# sch_design_easyEDA.net
KiCad netlist of a schematic drawn in EasyEDA
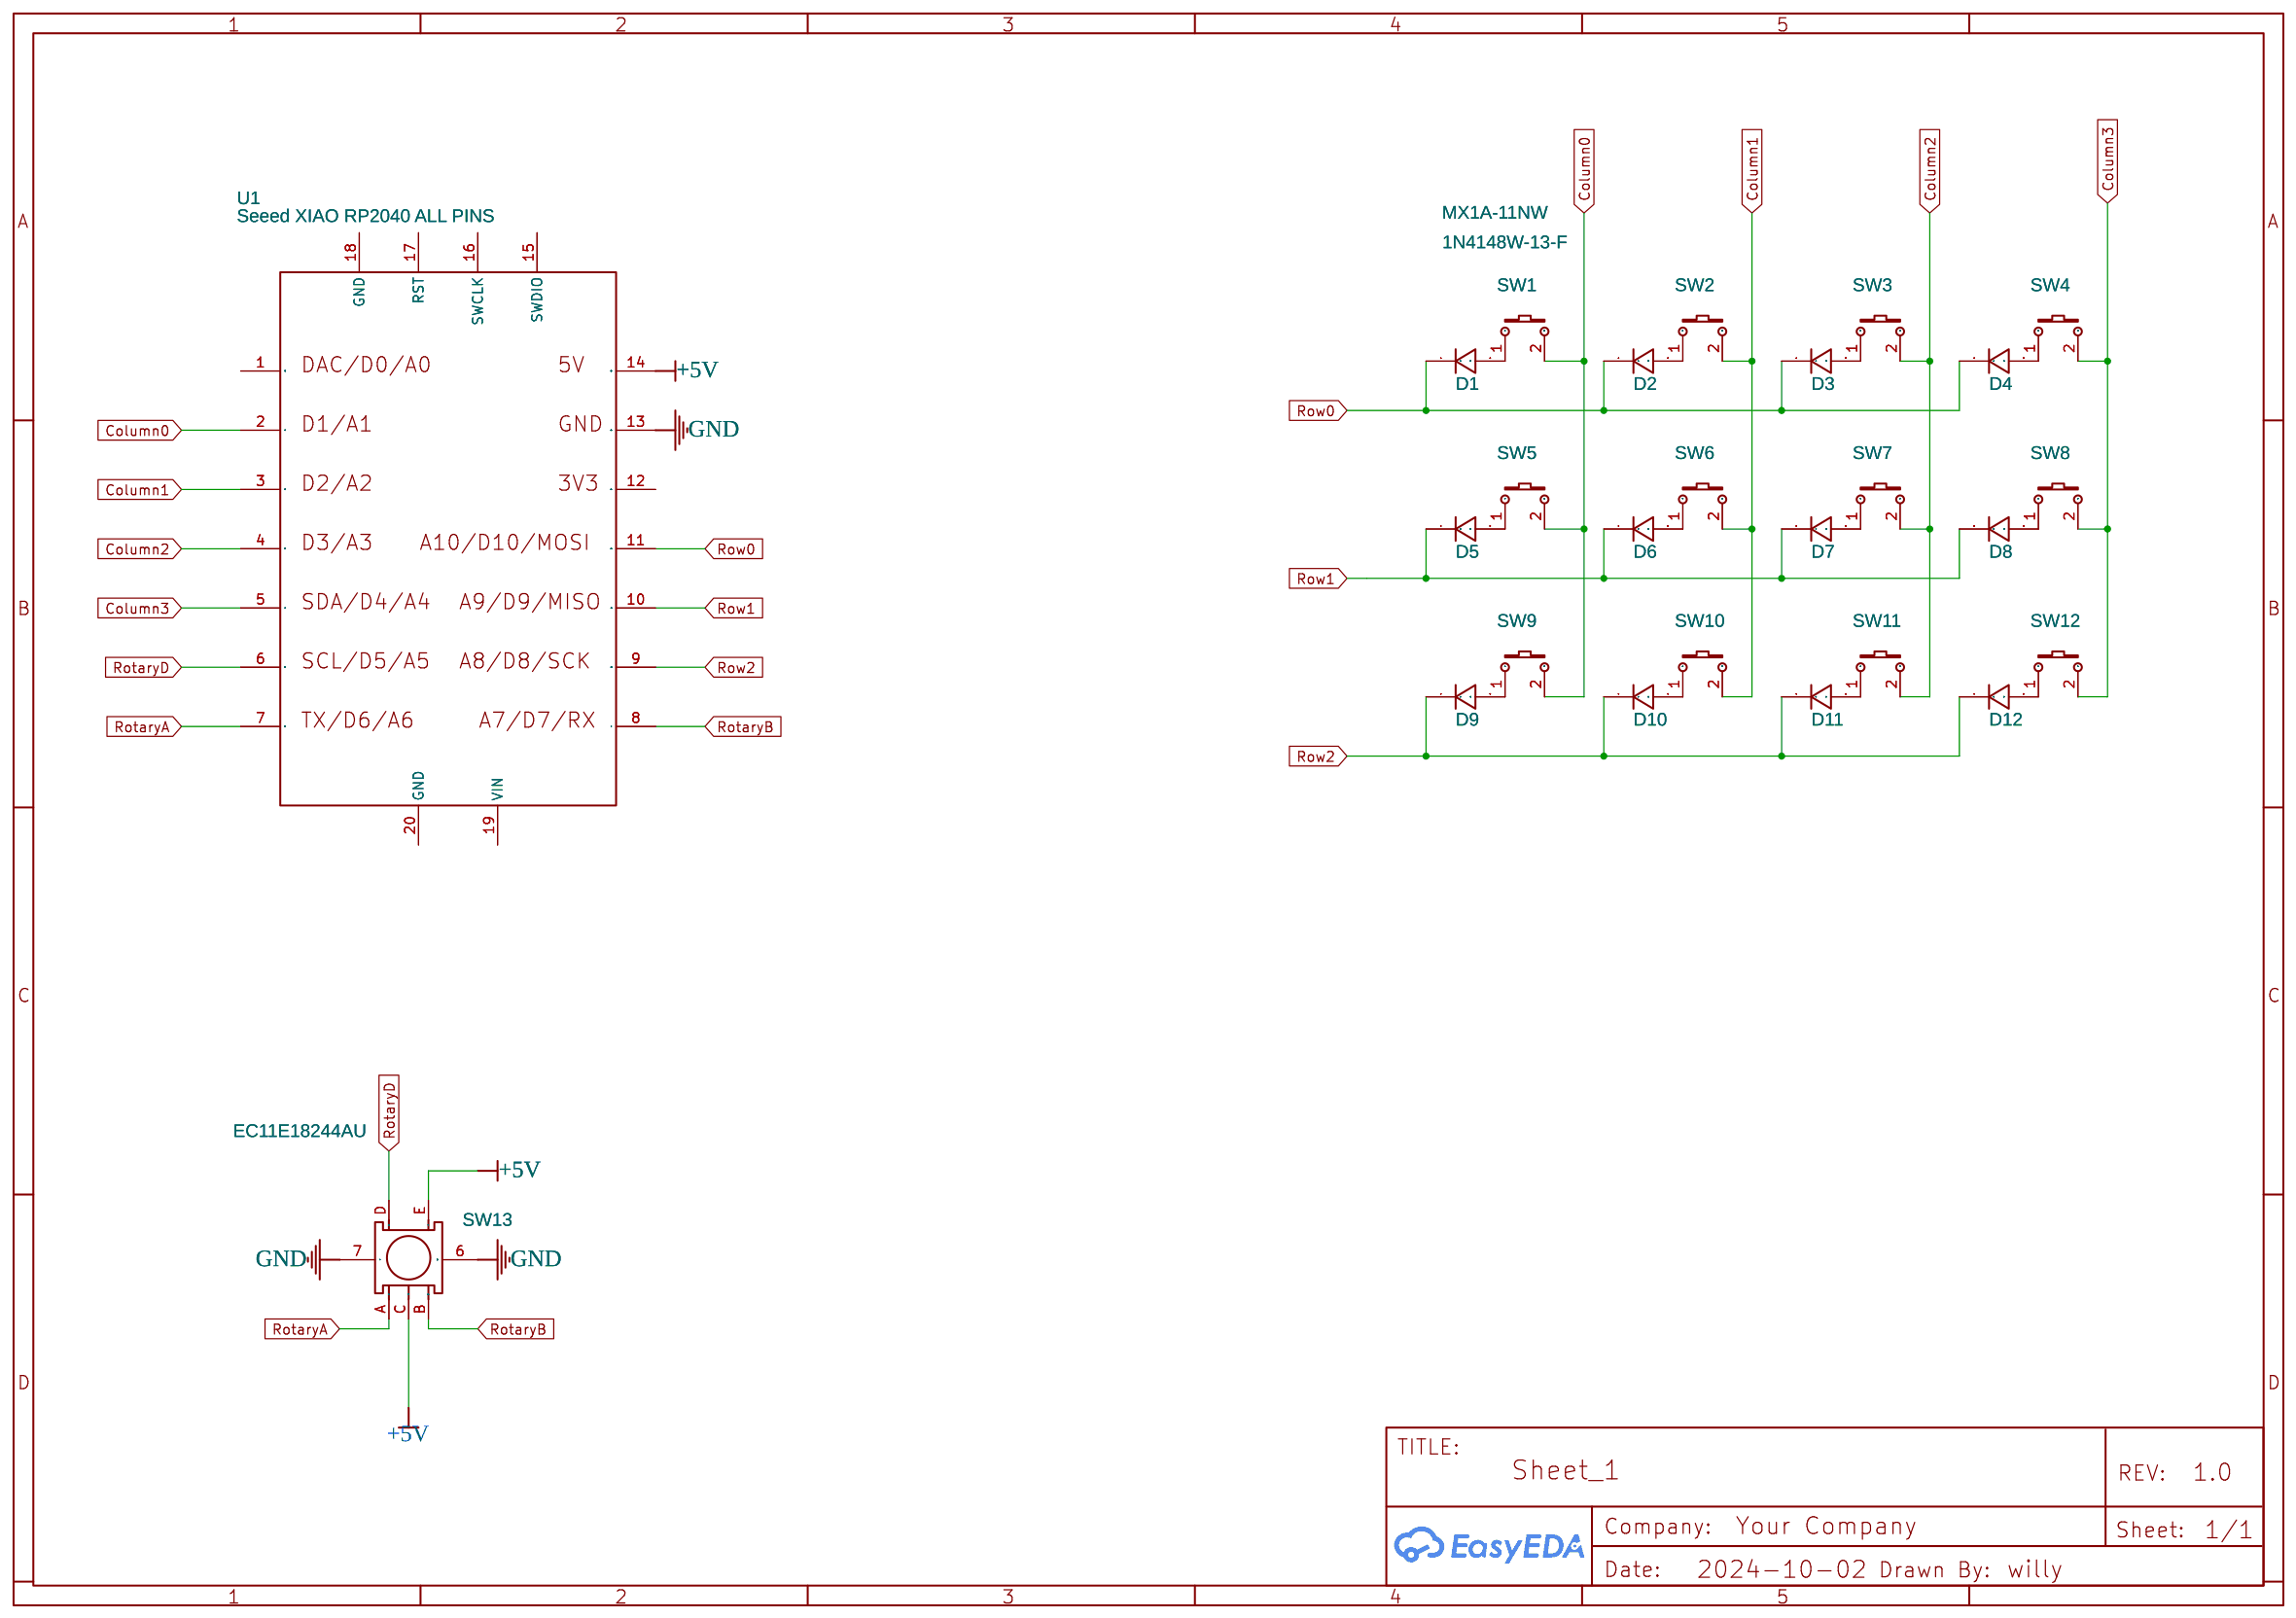
[diagram p0: schematic sheet]

(export (version "E")
  (design (tool "Eeschema 10.0.6"))
  (components
    (comp (ref "D1")
      (value "1N4148W-13-F")
      (fields (field (name "Manufacturer") "DIODES(美台)"))
      (libsource (lib "") (part "1N4148W-13-F"))
    )
    (comp (ref "D2")
      (value "1N4148W-13-F")
      (fields (field (name "Manufacturer") "DIODES(美台)"))
      (libsource (lib "") (part "1N4148W-13-F"))
    )
    (comp (ref "D3")
      (value "1N4148W-13-F")
      (fields (field (name "Manufacturer") "DIODES(美台)"))
      (libsource (lib "") (part "1N4148W-13-F"))
    )
    (comp (ref "D4")
      (value "1N4148W-13-F")
      (fields (field (name "Manufacturer") "DIODES(美台)"))
      (libsource (lib "") (part "1N4148W-13-F"))
    )
    (comp (ref "D5")
      (value "1N4148W-13-F")
      (fields (field (name "Manufacturer") "DIODES(美台)"))
      (libsource (lib "") (part "1N4148W-13-F"))
    )
    (comp (ref "D6")
      (value "1N4148W-13-F")
      (fields (field (name "Manufacturer") "DIODES(美台)"))
      (libsource (lib "") (part "1N4148W-13-F"))
    )
    (comp (ref "D7")
      (value "1N4148W-13-F")
      (fields (field (name "Manufacturer") "DIODES(美台)"))
      (libsource (lib "") (part "1N4148W-13-F"))
    )
    (comp (ref "D8")
      (value "1N4148W-13-F")
      (fields (field (name "Manufacturer") "DIODES(美台)"))
      (libsource (lib "") (part "1N4148W-13-F"))
    )
    (comp (ref "D9")
      (value "1N4148W-13-F")
      (fields (field (name "Manufacturer") "DIODES(美台)"))
      (libsource (lib "") (part "1N4148W-13-F"))
    )
    (comp (ref "D10")
      (value "1N4148W-13-F")
      (fields (field (name "Manufacturer") "DIODES(美台)"))
      (libsource (lib "") (part "1N4148W-13-F"))
    )
    (comp (ref "D11")
      (value "1N4148W-13-F")
      (fields (field (name "Manufacturer") "DIODES(美台)"))
      (libsource (lib "") (part "1N4148W-13-F"))
    )
    (comp (ref "D12")
      (value "1N4148W-13-F")
      (fields (field (name "Manufacturer") "DIODES(美台)"))
      (libsource (lib "") (part "1N4148W-13-F"))
    )
    (comp (ref "SW1")
      (value "MX1A-11NW")
      (fields (field (name "Manufacturer") "CHERRY"))
      (libsource (lib "") (part "MX1A-11NW"))
    )
    (comp (ref "SW2")
      (value "MX1A-11NW")
      (fields (field (name "Manufacturer") "CHERRY"))
      (libsource (lib "") (part "MX1A-11NW"))
    )
    (comp (ref "SW3")
      (value "MX1A-11NW")
      (fields (field (name "Manufacturer") "CHERRY"))
      (libsource (lib "") (part "MX1A-11NW"))
    )
    (comp (ref "SW4")
      (value "MX1A-11NW")
      (fields (field (name "Manufacturer") "CHERRY"))
      (libsource (lib "") (part "MX1A-11NW"))
    )
    (comp (ref "SW5")
      (value "MX1A-11NW")
      (fields (field (name "Manufacturer") "CHERRY"))
      (libsource (lib "") (part "MX1A-11NW"))
    )
    (comp (ref "SW6")
      (value "MX1A-11NW")
      (fields (field (name "Manufacturer") "CHERRY"))
      (libsource (lib "") (part "MX1A-11NW"))
    )
    (comp (ref "SW7")
      (value "MX1A-11NW")
      (fields (field (name "Manufacturer") "CHERRY"))
      (libsource (lib "") (part "MX1A-11NW"))
    )
    (comp (ref "SW8")
      (value "MX1A-11NW")
      (fields (field (name "Manufacturer") "CHERRY"))
      (libsource (lib "") (part "MX1A-11NW"))
    )
    (comp (ref "SW9")
      (value "MX1A-11NW")
      (fields (field (name "Manufacturer") "CHERRY"))
      (libsource (lib "") (part "MX1A-11NW"))
    )
    (comp (ref "SW10")
      (value "MX1A-11NW")
      (fields (field (name "Manufacturer") "CHERRY"))
      (libsource (lib "") (part "MX1A-11NW"))
    )
    (comp (ref "SW11")
      (value "MX1A-11NW")
      (fields (field (name "Manufacturer") "CHERRY"))
      (libsource (lib "") (part "MX1A-11NW"))
    )
    (comp (ref "SW12")
      (value "MX1A-11NW")
      (fields (field (name "Manufacturer") "CHERRY"))
      (libsource (lib "") (part "MX1A-11NW"))
    )
    (comp (ref "SW13")
      (value "EC11E18244AU")
      (fields (field (name "Manufacturer") "ALPSALPINE(阿尔卑斯阿尔派)"))
      (libsource (lib "") (part "EC11E18244AU"))
    )
    (comp (ref "U1")
      (value "Seeed XIAO RP2040 ALL PINS")
      (fields (field (name "Manufacturer Part") "102010328") (field (name "Manufacturer") "Seeedstudio"))
      (libsource (lib "") (part "Seeed XIAO RP2040 ALL PINS"))
    )
  )
  (nets
    (net (code "1") (name "+5V") (class "Default")
      (node (ref "SW13") (pin "C") (pinfunction "C_C") (pintype "unspecified"))
      (node (ref "SW13") (pin "E") (pinfunction "E_E") (pintype "unspecified"))
      (node (ref "U1") (pin "14") (pinfunction "13_14") (pintype "unspecified"))
    )
    (net (code "2") (name "Column0") (class "Default")
      (node (ref "SW1") (pin "2") (pinfunction "2_2") (pintype "unspecified"))
      (node (ref "SW5") (pin "2") (pinfunction "2_2") (pintype "unspecified"))
      (node (ref "SW9") (pin "2") (pinfunction "2_2") (pintype "unspecified"))
      (node (ref "U1") (pin "2") (pinfunction "1_2") (pintype "unspecified"))
    )
    (net (code "3") (name "Column1") (class "Default")
      (node (ref "SW10") (pin "2") (pinfunction "2_2") (pintype "unspecified"))
      (node (ref "SW2") (pin "2") (pinfunction "2_2") (pintype "unspecified"))
      (node (ref "SW6") (pin "2") (pinfunction "2_2") (pintype "unspecified"))
      (node (ref "U1") (pin "3") (pinfunction "2_3") (pintype "unspecified"))
    )
    (net (code "4") (name "Column2") (class "Default")
      (node (ref "SW11") (pin "2") (pinfunction "2_2") (pintype "unspecified"))
      (node (ref "SW3") (pin "2") (pinfunction "2_2") (pintype "unspecified"))
      (node (ref "SW7") (pin "2") (pinfunction "2_2") (pintype "unspecified"))
      (node (ref "U1") (pin "4") (pinfunction "3_4") (pintype "unspecified"))
    )
    (net (code "5") (name "Column3") (class "Default")
      (node (ref "SW12") (pin "2") (pinfunction "2_2") (pintype "unspecified"))
      (node (ref "SW4") (pin "2") (pinfunction "2_2") (pintype "unspecified"))
      (node (ref "SW8") (pin "2") (pinfunction "2_2") (pintype "unspecified"))
      (node (ref "U1") (pin "5") (pinfunction "4_5") (pintype "unspecified"))
    )
    (net (code "6") (name "GND") (class "Default")
      (node (ref "SW13") (pin "6") (pinfunction "6_6") (pintype "unspecified"))
      (node (ref "SW13") (pin "7") (pinfunction "7_7") (pintype "unspecified"))
      (node (ref "U1") (pin "13") (pinfunction "12_13") (pintype "unspecified"))
    )
    (net (code "7") (name "Net-(D1-Pad2)") (class "Default")
      (node (ref "D1") (pin "2") (pinfunction "2_2") (pintype "unspecified"))
      (node (ref "SW1") (pin "1") (pinfunction "1_1") (pintype "unspecified"))
    )
    (net (code "8") (name "Net-(D2-Pad2)") (class "Default")
      (node (ref "D2") (pin "2") (pinfunction "2_2") (pintype "unspecified"))
      (node (ref "SW2") (pin "1") (pinfunction "1_1") (pintype "unspecified"))
    )
    (net (code "9") (name "Net-(D3-Pad2)") (class "Default")
      (node (ref "D3") (pin "2") (pinfunction "2_2") (pintype "unspecified"))
      (node (ref "SW3") (pin "1") (pinfunction "1_1") (pintype "unspecified"))
    )
    (net (code "10") (name "Net-(D4-Pad2)") (class "Default")
      (node (ref "D4") (pin "2") (pinfunction "2_2") (pintype "unspecified"))
      (node (ref "SW4") (pin "1") (pinfunction "1_1") (pintype "unspecified"))
    )
    (net (code "11") (name "Net-(D5-Pad2)") (class "Default")
      (node (ref "D5") (pin "2") (pinfunction "2_2") (pintype "unspecified"))
      (node (ref "SW5") (pin "1") (pinfunction "1_1") (pintype "unspecified"))
    )
    (net (code "12") (name "Net-(D6-Pad2)") (class "Default")
      (node (ref "D6") (pin "2") (pinfunction "2_2") (pintype "unspecified"))
      (node (ref "SW6") (pin "1") (pinfunction "1_1") (pintype "unspecified"))
    )
    (net (code "13") (name "Net-(D7-Pad2)") (class "Default")
      (node (ref "D7") (pin "2") (pinfunction "2_2") (pintype "unspecified"))
      (node (ref "SW7") (pin "1") (pinfunction "1_1") (pintype "unspecified"))
    )
    (net (code "14") (name "Net-(D8-Pad2)") (class "Default")
      (node (ref "D8") (pin "2") (pinfunction "2_2") (pintype "unspecified"))
      (node (ref "SW8") (pin "1") (pinfunction "1_1") (pintype "unspecified"))
    )
    (net (code "15") (name "Net-(D9-Pad2)") (class "Default")
      (node (ref "D9") (pin "2") (pinfunction "2_2") (pintype "unspecified"))
      (node (ref "SW9") (pin "1") (pinfunction "1_1") (pintype "unspecified"))
    )
    (net (code "16") (name "Net-(D10-Pad2)") (class "Default")
      (node (ref "D10") (pin "2") (pinfunction "2_2") (pintype "unspecified"))
      (node (ref "SW10") (pin "1") (pinfunction "1_1") (pintype "unspecified"))
    )
    (net (code "17") (name "Net-(D11-Pad2)") (class "Default")
      (node (ref "D11") (pin "2") (pinfunction "2_2") (pintype "unspecified"))
      (node (ref "SW11") (pin "1") (pinfunction "1_1") (pintype "unspecified"))
    )
    (net (code "18") (name "Net-(D12-Pad2)") (class "Default")
      (node (ref "D12") (pin "2") (pinfunction "2_2") (pintype "unspecified"))
      (node (ref "SW12") (pin "1") (pinfunction "1_1") (pintype "unspecified"))
    )
    (net (code "19") (name "RotaryA") (class "Default")
      (node (ref "SW13") (pin "A") (pinfunction "A_A") (pintype "unspecified"))
      (node (ref "U1") (pin "7") (pinfunction "6_7") (pintype "unspecified"))
    )
    (net (code "20") (name "RotaryB") (class "Default")
      (node (ref "SW13") (pin "B") (pinfunction "B_B") (pintype "unspecified"))
      (node (ref "U1") (pin "8") (pinfunction "7_8") (pintype "unspecified"))
    )
    (net (code "21") (name "RotaryD") (class "Default")
      (node (ref "SW13") (pin "D") (pinfunction "D_D") (pintype "unspecified"))
      (node (ref "U1") (pin "6") (pinfunction "5_6") (pintype "unspecified"))
    )
    (net (code "22") (name "Row0") (class "Default")
      (node (ref "D1") (pin "1") (pinfunction "1_1") (pintype "unspecified"))
      (node (ref "D2") (pin "1") (pinfunction "1_1") (pintype "unspecified"))
      (node (ref "D3") (pin "1") (pinfunction "1_1") (pintype "unspecified"))
      (node (ref "D4") (pin "1") (pinfunction "1_1") (pintype "unspecified"))
      (node (ref "U1") (pin "11") (pinfunction "10_11") (pintype "unspecified"))
    )
    (net (code "23") (name "Row1") (class "Default")
      (node (ref "D5") (pin "1") (pinfunction "1_1") (pintype "unspecified"))
      (node (ref "D6") (pin "1") (pinfunction "1_1") (pintype "unspecified"))
      (node (ref "D7") (pin "1") (pinfunction "1_1") (pintype "unspecified"))
      (node (ref "D8") (pin "1") (pinfunction "1_1") (pintype "unspecified"))
      (node (ref "U1") (pin "10") (pinfunction "9_10") (pintype "unspecified"))
    )
    (net (code "24") (name "Row2") (class "Default")
      (node (ref "D10") (pin "1") (pinfunction "1_1") (pintype "unspecified"))
      (node (ref "D11") (pin "1") (pinfunction "1_1") (pintype "unspecified"))
      (node (ref "D12") (pin "1") (pinfunction "1_1") (pintype "unspecified"))
      (node (ref "D9") (pin "1") (pinfunction "1_1") (pintype "unspecified"))
      (node (ref "U1") (pin "9") (pinfunction "8_9") (pintype "unspecified"))
    )
    (net (code "25") (name "unconnected-(U1-0-Pad1)") (class "Default")
      (node (ref "U1") (pin "1") (pinfunction "0_1") (pintype "unspecified"))
    )
    (net (code "26") (name "unconnected-(U1-11-Pad12)") (class "Default")
      (node (ref "U1") (pin "12") (pinfunction "11_12") (pintype "unspecified"))
    )
    (net (code "27") (name "unconnected-(U1-GND-Pad18)") (class "Default")
      (node (ref "U1") (pin "18") (pinfunction "GND_18") (pintype "unspecified"))
    )
    (net (code "28") (name "unconnected-(U1-GND-Pad20)") (class "Default")
      (node (ref "U1") (pin "20") (pinfunction "GND_20") (pintype "unspecified"))
    )
    (net (code "29") (name "unconnected-(U1-RST-Pad17)") (class "Default")
      (node (ref "U1") (pin "17") (pinfunction "RST_17") (pintype "unspecified"))
    )
    (net (code "30") (name "unconnected-(U1-SWCLK-Pad16)") (class "Default")
      (node (ref "U1") (pin "16") (pinfunction "SWCLK_16") (pintype "unspecified"))
    )
    (net (code "31") (name "unconnected-(U1-SWDIO-Pad15)") (class "Default")
      (node (ref "U1") (pin "15") (pinfunction "SWDIO_15") (pintype "unspecified"))
    )
    (net (code "32") (name "unconnected-(U1-VIN-Pad19)") (class "Default")
      (node (ref "U1") (pin "19") (pinfunction "VIN_19") (pintype "unspecified"))
    )
  )
)
